# PB_Conn.net
KiCad netlist of a schematic drawn in Altium Designer
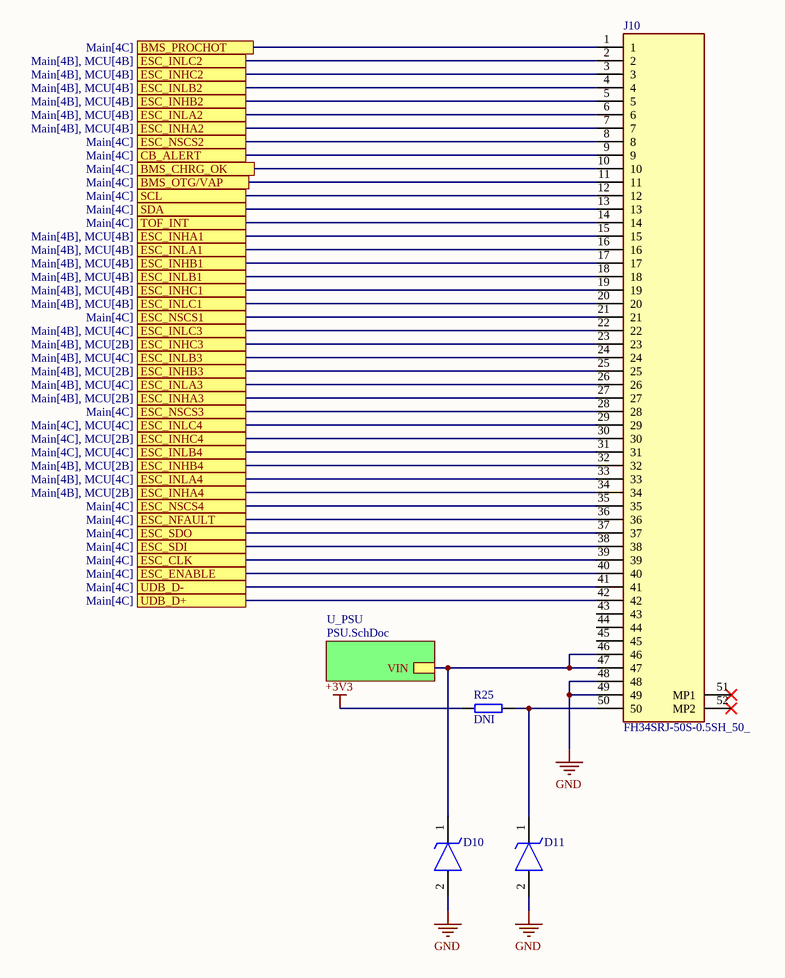
[diagram p0: PB_Conn.SchDoc]

(export (version "E")
  (design (tool "Eeschema 10.0.6"))
  (components
    (comp (ref "D10")
      (value "DF2S24FS,L3M")
      (footprint "SamacSys:SODFL1006X45N")
      (description "TVS Diode (Uni-directional)")
      (fields (field (name "MOUSER PART NUMBER") "757-DF2S24FSL3M"))
      (libsource (lib "*") (part "DF2S24FS,L3M"))
    )
    (comp (ref "D11")
      (value "DF2S24FS,L3M")
      (footprint "SamacSys:SODFL1006X45N")
      (description "TVS Diode (Uni-directional)")
      (fields (field (name "MOUSER PART NUMBER") "757-DF2S24FSL3M"))
      (libsource (lib "*") (part "DF2S24FS,L3M"))
    )
    (comp (ref "J10")
      (value "FH34SRJ-50S-0.5SH_50_")
      (footprint "SamacSys:FH34SRJ50S05SH50")
      (description "Connector")
      (fields
        (field (name "MANUFACTURER_PART_NUMBER") "FH34SRJ-50S-0.5SH(50)")
        (field (name "MOUSER PART NUMBER") "798-FH34SRJ50S05SH50")
      )
      (libsource (lib "*") (part "FH34SRJ-50S-0.5SH_50_"))
    )
    (comp (ref "R25")
      (value "DNI")
      (footprint "RES0402")
      (fields (field (name "Comment") "Res0402"))
      (libsource (lib "resistorSMD") (part "Res0402"))
    )
  )
  (nets
    (net (code "1") (name "+3V3") (class "Default")
      (node (ref "R25") (pin "2") (pinfunction "2_2") (pintype "passive"))
    )
    (net (code "2") (name "/BMS_CHRG_OK") (class "Default")
      (node (ref "J10") (pin "10") (pinfunction "10_10") (pintype "passive"))
    )
    (net (code "3") (name "/BMS_OTG{slash}VAP") (class "Default")
      (node (ref "J10") (pin "11") (pinfunction "11_11") (pintype "passive"))
    )
    (net (code "4") (name "/BMS_PROCHOT") (class "Default")
      (node (ref "J10") (pin "1") (pinfunction "1_1") (pintype "passive"))
    )
    (net (code "5") (name "/CB_ALERT") (class "Default")
      (node (ref "J10") (pin "9") (pinfunction "9_9") (pintype "passive"))
    )
    (net (code "6") (name "/ESC_CLK") (class "Default")
      (node (ref "J10") (pin "39") (pinfunction "39_39") (pintype "passive"))
    )
    (net (code "7") (name "/ESC_ENABLE") (class "Default")
      (node (ref "J10") (pin "40") (pinfunction "40_40") (pintype "passive"))
    )
    (net (code "8") (name "/ESC_INHA1") (class "Default")
      (node (ref "J10") (pin "15") (pinfunction "15_15") (pintype "passive"))
    )
    (net (code "9") (name "/ESC_INHA2") (class "Default")
      (node (ref "J10") (pin "7") (pinfunction "7_7") (pintype "passive"))
    )
    (net (code "10") (name "/ESC_INHA3") (class "Default")
      (node (ref "J10") (pin "27") (pinfunction "27_27") (pintype "passive"))
    )
    (net (code "11") (name "/ESC_INHA4") (class "Default")
      (node (ref "J10") (pin "34") (pinfunction "34_34") (pintype "passive"))
    )
    (net (code "12") (name "/ESC_INHB1") (class "Default")
      (node (ref "J10") (pin "17") (pinfunction "17_17") (pintype "passive"))
    )
    (net (code "13") (name "/ESC_INHB2") (class "Default")
      (node (ref "J10") (pin "5") (pinfunction "5_5") (pintype "passive"))
    )
    (net (code "14") (name "/ESC_INHB3") (class "Default")
      (node (ref "J10") (pin "25") (pinfunction "25_25") (pintype "passive"))
    )
    (net (code "15") (name "/ESC_INHB4") (class "Default")
      (node (ref "J10") (pin "32") (pinfunction "32_32") (pintype "passive"))
    )
    (net (code "16") (name "/ESC_INHC1") (class "Default")
      (node (ref "J10") (pin "19") (pinfunction "19_19") (pintype "passive"))
    )
    (net (code "17") (name "/ESC_INHC2") (class "Default")
      (node (ref "J10") (pin "3") (pinfunction "3_3") (pintype "passive"))
    )
    (net (code "18") (name "/ESC_INHC3") (class "Default")
      (node (ref "J10") (pin "23") (pinfunction "23_23") (pintype "passive"))
    )
    (net (code "19") (name "/ESC_INHC4") (class "Default")
      (node (ref "J10") (pin "30") (pinfunction "30_30") (pintype "passive"))
    )
    (net (code "20") (name "/ESC_INLA1") (class "Default")
      (node (ref "J10") (pin "16") (pinfunction "16_16") (pintype "passive"))
    )
    (net (code "21") (name "/ESC_INLA2") (class "Default")
      (node (ref "J10") (pin "6") (pinfunction "6_6") (pintype "passive"))
    )
    (net (code "22") (name "/ESC_INLA3") (class "Default")
      (node (ref "J10") (pin "26") (pinfunction "26_26") (pintype "passive"))
    )
    (net (code "23") (name "/ESC_INLA4") (class "Default")
      (node (ref "J10") (pin "33") (pinfunction "33_33") (pintype "passive"))
    )
    (net (code "24") (name "/ESC_INLB1") (class "Default")
      (node (ref "J10") (pin "18") (pinfunction "18_18") (pintype "passive"))
    )
    (net (code "25") (name "/ESC_INLB2") (class "Default")
      (node (ref "J10") (pin "4") (pinfunction "4_4") (pintype "passive"))
    )
    (net (code "26") (name "/ESC_INLB3") (class "Default")
      (node (ref "J10") (pin "24") (pinfunction "24_24") (pintype "passive"))
    )
    (net (code "27") (name "/ESC_INLB4") (class "Default")
      (node (ref "J10") (pin "31") (pinfunction "31_31") (pintype "passive"))
    )
    (net (code "28") (name "/ESC_INLC1") (class "Default")
      (node (ref "J10") (pin "20") (pinfunction "20_20") (pintype "passive"))
    )
    (net (code "29") (name "/ESC_INLC2") (class "Default")
      (node (ref "J10") (pin "2") (pinfunction "2_2") (pintype "passive"))
    )
    (net (code "30") (name "/ESC_INLC3") (class "Default")
      (node (ref "J10") (pin "22") (pinfunction "22_22") (pintype "passive"))
    )
    (net (code "31") (name "/ESC_INLC4") (class "Default")
      (node (ref "J10") (pin "29") (pinfunction "29_29") (pintype "passive"))
    )
    (net (code "32") (name "/ESC_NFAULT") (class "Default")
      (node (ref "J10") (pin "36") (pinfunction "36_36") (pintype "passive"))
    )
    (net (code "33") (name "/ESC_NSCS1") (class "Default")
      (node (ref "J10") (pin "21") (pinfunction "21_21") (pintype "passive"))
    )
    (net (code "34") (name "/ESC_NSCS2") (class "Default")
      (node (ref "J10") (pin "8") (pinfunction "8_8") (pintype "passive"))
    )
    (net (code "35") (name "/ESC_NSCS3") (class "Default")
      (node (ref "J10") (pin "28") (pinfunction "28_28") (pintype "passive"))
    )
    (net (code "36") (name "/ESC_NSCS4") (class "Default")
      (node (ref "J10") (pin "35") (pinfunction "35_35") (pintype "passive"))
    )
    (net (code "37") (name "/ESC_SDI") (class "Default")
      (node (ref "J10") (pin "38") (pinfunction "38_38") (pintype "passive"))
    )
    (net (code "38") (name "/ESC_SDO") (class "Default")
      (node (ref "J10") (pin "37") (pinfunction "37_37") (pintype "passive"))
    )
    (net (code "39") (name "/SCL") (class "Default")
      (node (ref "J10") (pin "12") (pinfunction "12_12") (pintype "passive"))
    )
    (net (code "40") (name "/SDA") (class "Default")
      (node (ref "J10") (pin "13") (pinfunction "13_13") (pintype "passive"))
    )
    (net (code "41") (name "/TOF_INT") (class "Default")
      (node (ref "J10") (pin "14") (pinfunction "14_14") (pintype "passive"))
    )
    (net (code "42") (name "/UDB_D+") (class "Default")
      (node (ref "J10") (pin "42") (pinfunction "42_42") (pintype "passive"))
    )
    (net (code "43") (name "/UDB_D-") (class "Default")
      (node (ref "J10") (pin "41") (pinfunction "41_41") (pintype "passive"))
    )
    (net (code "44") (name "/VIN") (class "Default")
      (node (ref "D10") (pin "1") (pinfunction "K_1") (pintype "passive"))
      (node (ref "J10") (pin "46") (pinfunction "46_46") (pintype "passive"))
      (node (ref "J10") (pin "47") (pinfunction "47_47") (pintype "passive"))
    )
    (net (code "45") (name "GND") (class "Default")
      (node (ref "D10") (pin "2") (pinfunction "A_2") (pintype "passive"))
      (node (ref "D11") (pin "2") (pinfunction "A_2") (pintype "passive"))
      (node (ref "J10") (pin "48") (pinfunction "48_48") (pintype "passive"))
      (node (ref "J10") (pin "49") (pinfunction "49_49") (pintype "passive"))
    )
    (net (code "46") (name "Net-(D11-K)") (class "Default")
      (node (ref "D11") (pin "1") (pinfunction "K_1") (pintype "passive"))
      (node (ref "J10") (pin "50") (pinfunction "50_50") (pintype "passive"))
      (node (ref "R25") (pin "1") (pinfunction "1_1") (pintype "passive"))
    )
    (net (code "47") (name "unconnected-(J10-MP1-Pad51)") (class "Default")
      (node (ref "J10") (pin "51") (pinfunction "MP1_51") (pintype "passive+no_connect"))
    )
    (net (code "48") (name "unconnected-(J10-MP2-Pad52)") (class "Default")
      (node (ref "J10") (pin "52") (pinfunction "MP2_52") (pintype "passive+no_connect"))
    )
    (net (code "49") (name "unconnected-(J10-Pad43)") (class "Default")
      (node (ref "J10") (pin "43") (pinfunction "43_43") (pintype "passive"))
    )
    (net (code "50") (name "unconnected-(J10-Pad44)") (class "Default")
      (node (ref "J10") (pin "44") (pinfunction "44_44") (pintype "passive"))
    )
    (net (code "51") (name "unconnected-(J10-Pad45)") (class "Default")
      (node (ref "J10") (pin "45") (pinfunction "45_45") (pintype "passive"))
    )
  )
)
